# alim_logique_hard.net
KiCad netlist of a schematic drawn in Altium Designer
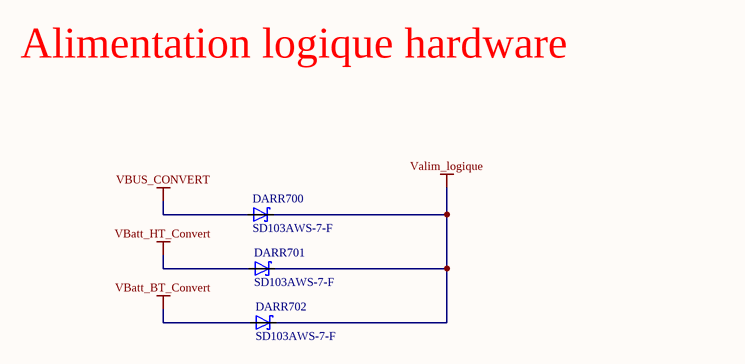
[diagram p0: alim_logique_hard.SchDoc]

(export (version "E")
  (design (tool "Eeschema 10.0.6"))
  (components
    (comp (ref "DARR700")
      (value "SD103AWS-7-F")
      (footprint "SD103AWS-7-F")
      (description "Diode Array 3 Independent Schottky 40V 175mA Surface Mount 6-TSSOP, SC-88, SOT-363")
      (libsource (lib "SCHLibrary") (part "SD103AWS-7-F"))
    )
    (comp (ref "DARR701")
      (value "SD103AWS-7-F")
      (footprint "SD103AWS-7-F")
      (description "Diode Array 3 Independent Schottky 40V 175mA Surface Mount 6-TSSOP, SC-88, SOT-363")
      (libsource (lib "SCHLibrary") (part "SD103AWS-7-F"))
    )
    (comp (ref "DARR702")
      (value "SD103AWS-7-F")
      (footprint "SD103AWS-7-F")
      (description "Diode Array 3 Independent Schottky 40V 175mA Surface Mount 6-TSSOP, SC-88, SOT-363")
      (libsource (lib "SCHLibrary") (part "SD103AWS-7-F"))
    )
  )
  (nets
    (net (code "1") (name "VBUS_CONVERT") (class "Default")
      (node (ref "DARR700") (pin "2") (pinfunction "A_2") (pintype "passive"))
    )
    (net (code "2") (name "VBatt_BT_Convert") (class "Default")
      (node (ref "DARR702") (pin "2") (pinfunction "A_2") (pintype "passive"))
    )
    (net (code "3") (name "VBatt_HT_Convert") (class "Default")
      (node (ref "DARR701") (pin "2") (pinfunction "A_2") (pintype "passive"))
    )
    (net (code "4") (name "Valim_logique") (class "Default")
      (node (ref "DARR700") (pin "1") (pinfunction "C_1") (pintype "passive"))
      (node (ref "DARR701") (pin "1") (pinfunction "C_1") (pintype "passive"))
      (node (ref "DARR702") (pin "1") (pinfunction "C_1") (pintype "passive"))
    )
  )
)
